# pi-crust14.net
KiCad netlist of a schematic drawn in EAGLE
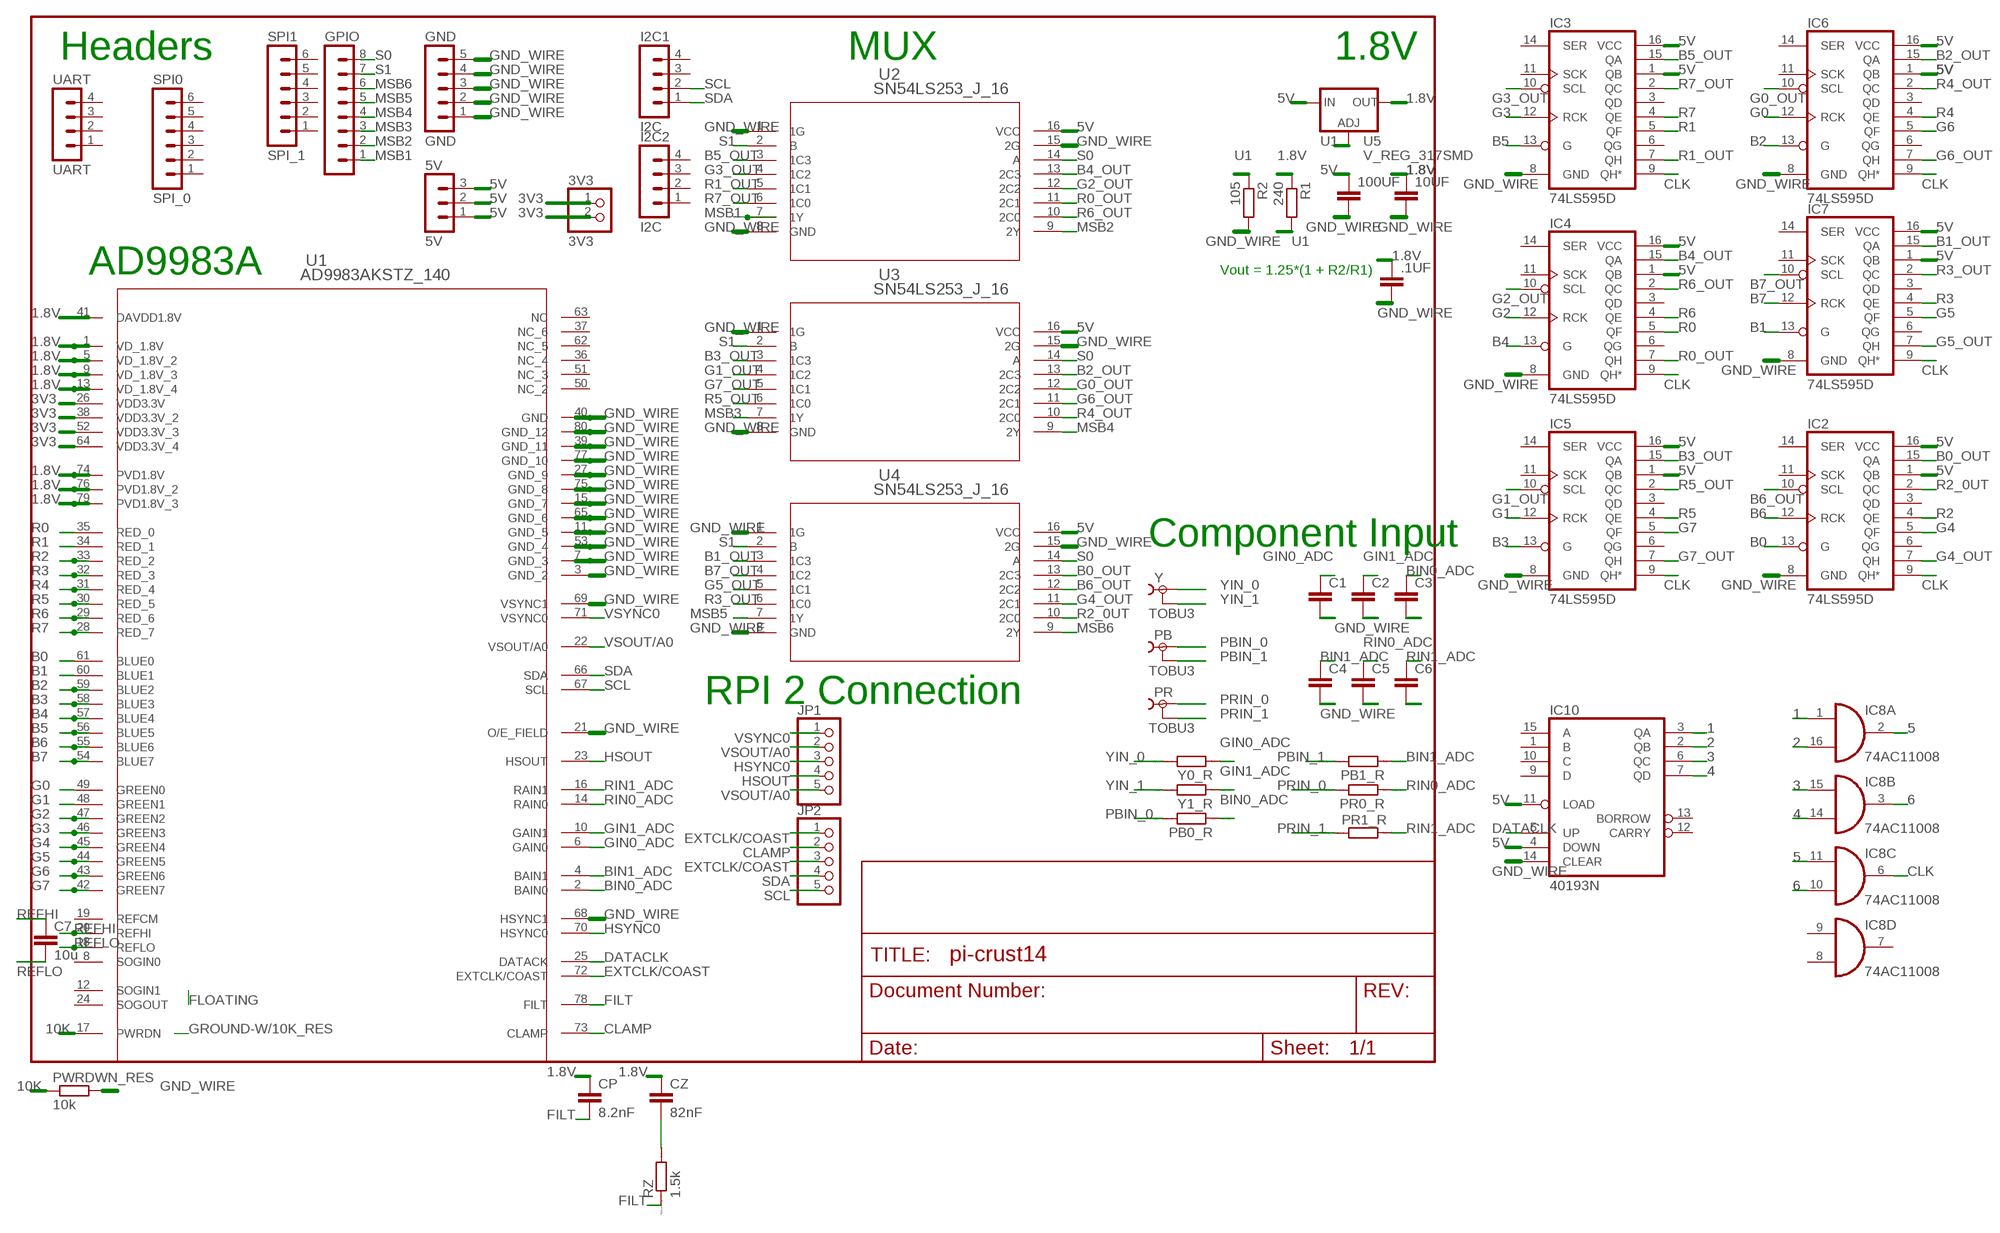
[diagram p0: schematic, sheet 1]

(export (version "E")
  (design (tool "Eeschema 10.0.6"))
  (components
    (comp (ref ".1UF")
      (value "C2.5/5")
      (footprint "eagle-import:C2.5-5")
      (libsource (lib "eagle-import") (part "C2.5/5"))
    )
    (comp (ref "3V3")
      (value "3V3")
      (footprint "eagle-import:1X02")
      (libsource (lib "eagle-import") (part "PINHD-1X2"))
    )
    (comp (ref "5V")
      (value "5V")
      (footprint "eagle-import:MA03-1")
      (libsource (lib "eagle-import") (part "MA03-1"))
    )
    (comp (ref "10UF")
      (value "C2.5/5")
      (footprint "eagle-import:C2.5-5")
      (libsource (lib "eagle-import") (part "C2.5/5"))
    )
    (comp (ref "100UF")
      (value "C2.5/5")
      (footprint "eagle-import:C2.5-5")
      (libsource (lib "eagle-import") (part "C2.5/5"))
    )
    (comp (ref "C1")
      (value "C2.5/5")
      (footprint "eagle-import:C2.5-5")
      (libsource (lib "eagle-import") (part "C2.5/5"))
    )
    (comp (ref "C2")
      (value "C2.5/5")
      (footprint "eagle-import:C2.5-5")
      (libsource (lib "eagle-import") (part "C2.5/5"))
    )
    (comp (ref "C3")
      (value "C2.5/5")
      (footprint "eagle-import:C2.5-5")
      (libsource (lib "eagle-import") (part "C2.5/5"))
    )
    (comp (ref "C4")
      (value "C2.5/5")
      (footprint "eagle-import:C2.5-5")
      (libsource (lib "eagle-import") (part "C2.5/5"))
    )
    (comp (ref "C5")
      (value "C2.5/5")
      (footprint "eagle-import:C2.5-5")
      (libsource (lib "eagle-import") (part "C2.5/5"))
    )
    (comp (ref "C6")
      (value "C2.5/5")
      (footprint "eagle-import:C2.5-5")
      (libsource (lib "eagle-import") (part "C2.5/5"))
    )
    (comp (ref "C7")
      (value "10u")
      (footprint "eagle-import:C2.5-5")
      (libsource (lib "eagle-import") (part "C2.5/5"))
    )
    (comp (ref "CP")
      (value "8.2nF")
      (footprint "eagle-import:C2.5-5")
      (libsource (lib "eagle-import") (part "C2.5/5"))
    )
    (comp (ref "CZ")
      (value "82nF")
      (footprint "eagle-import:C2.5-5")
      (libsource (lib "eagle-import") (part "C2.5/5"))
    )
    (comp (ref "GND")
      (value "GND")
      (footprint "eagle-import:MA05-1")
      (libsource (lib "eagle-import") (part "MA05-1"))
    )
    (comp (ref "GPIO")
      (value "MA08-1")
      (footprint "eagle-import:MA08-1")
      (libsource (lib "eagle-import") (part "MA08-1"))
    )
    (comp (ref "I2C1")
      (value "I2C")
      (footprint "eagle-import:MA04-1")
      (libsource (lib "eagle-import") (part "MA04-1"))
    )
    (comp (ref "I2C2")
      (value "I2C")
      (footprint "eagle-import:MA04-1")
      (libsource (lib "eagle-import") (part "MA04-1"))
    )
    (comp (ref "IC2")
      (value "74LS595D")
      (footprint "eagle-import:SO16")
      (libsource (lib "eagle-import") (part "74595DLS"))
    )
    (comp (ref "IC3")
      (value "74LS595D")
      (footprint "eagle-import:SO16")
      (libsource (lib "eagle-import") (part "74595DLS"))
    )
    (comp (ref "IC4")
      (value "74LS595D")
      (footprint "eagle-import:SO16")
      (libsource (lib "eagle-import") (part "74595DLS"))
    )
    (comp (ref "IC5")
      (value "74LS595D")
      (footprint "eagle-import:SO16")
      (libsource (lib "eagle-import") (part "74595DLS"))
    )
    (comp (ref "IC6")
      (value "74LS595D")
      (footprint "eagle-import:SO16")
      (libsource (lib "eagle-import") (part "74595DLS"))
    )
    (comp (ref "IC7")
      (value "74LS595D")
      (footprint "eagle-import:SO16")
      (libsource (lib "eagle-import") (part "74595DLS"))
    )
    (comp (ref "IC8")
      (value "74AC11008")
      (footprint "eagle-import:DIL16")
      (libsource (lib "eagle-import") (part "74AC11008"))
    )
    (comp (ref "IC10")
      (value "40193N")
      (footprint "eagle-import:DIL16")
      (libsource (lib "eagle-import") (part "40193N"))
    )
    (comp (ref "JP1")
      (value "PINHD-1X5")
      (footprint "eagle-import:1X05")
      (libsource (lib "eagle-import") (part "PINHD-1X5"))
    )
    (comp (ref "JP2")
      (value "PINHD-1X5")
      (footprint "eagle-import:1X05")
      (libsource (lib "eagle-import") (part "PINHD-1X5"))
    )
    (comp (ref "PB")
      (value "TOBU3")
      (footprint "eagle-import:TOBU3")
      (fields (field (name "MF") "FARNELL") (field (name "MPN") "TOBU 3"))
      (libsource (lib "eagle-import") (part "TOBU3"))
    )
    (comp (ref "PB0_R")
      (value "R0204/7")
      (footprint "eagle-import:0204_7")
      (libsource (lib "eagle-import") (part "R0204/7"))
    )
    (comp (ref "PB1_R")
      (value "R0204/7")
      (footprint "eagle-import:0204_7")
      (libsource (lib "eagle-import") (part "R0204/7"))
    )
    (comp (ref "PR")
      (value "TOBU3")
      (footprint "eagle-import:TOBU3")
      (fields (field (name "MF") "FARNELL") (field (name "MPN") "TOBU 3"))
      (libsource (lib "eagle-import") (part "TOBU3"))
    )
    (comp (ref "PR0_R")
      (value "R0204/7")
      (footprint "eagle-import:0204_7")
      (libsource (lib "eagle-import") (part "R0204/7"))
    )
    (comp (ref "PR1_R")
      (value "R0204/7")
      (footprint "eagle-import:0204_7")
      (libsource (lib "eagle-import") (part "R0204/7"))
    )
    (comp (ref "PWRDWN_RES")
      (value "10k")
      (footprint "eagle-import:0204_7")
      (libsource (lib "eagle-import") (part "R-EU_0204/7"))
    )
    (comp (ref "R1")
      (value "240")
      (footprint "eagle-import:0204_7")
      (libsource (lib "eagle-import") (part "R-EU_0204/7"))
    )
    (comp (ref "R2")
      (value "105")
      (footprint "eagle-import:0204_7")
      (libsource (lib "eagle-import") (part "R-EU_0204/7"))
    )
    (comp (ref "RZ")
      (value "1.5k")
      (footprint "eagle-import:0204_7")
      (libsource (lib "eagle-import") (part "R0204/7"))
    )
    (comp (ref "SPI0")
      (value "SPI_0")
      (footprint "eagle-import:MA06-1")
      (libsource (lib "eagle-import") (part "MA06-1"))
    )
    (comp (ref "SPI1")
      (value "SPI_1")
      (footprint "eagle-import:MA06-1")
      (libsource (lib "eagle-import") (part "MA06-1"))
    )
    (comp (ref "U1")
      (value "AD9983AKSTZ_140")
      (footprint "eagle-import:ST_80_2")
      (libsource (lib "eagle-import") (part "AD9983AKSTZ_140"))
    )
    (comp (ref "U2")
      (value "SN54LS253_J_16")
      (footprint "eagle-import:J16")
      (fields
        (field (name "GENERIC_PART_NUMBER") "SN54LS253")
        (field (name "MANUFACTURER") "Texas Instruments")
      )
      (libsource (lib "eagle-import") (part "SN54LS253_J_16"))
    )
    (comp (ref "U3")
      (value "SN54LS253_J_16")
      (footprint "eagle-import:J16")
      (fields
        (field (name "GENERIC_PART_NUMBER") "SN54LS253")
        (field (name "MANUFACTURER") "Texas Instruments")
      )
      (libsource (lib "eagle-import") (part "SN54LS253_J_16"))
    )
    (comp (ref "U4")
      (value "SN54LS253_J_16")
      (footprint "eagle-import:J16")
      (fields
        (field (name "GENERIC_PART_NUMBER") "SN54LS253")
        (field (name "MANUFACTURER") "Texas Instruments")
      )
      (libsource (lib "eagle-import") (part "SN54LS253_J_16"))
    )
    (comp (ref "U5")
      (value "V_REG_317SMD")
      (footprint "eagle-import:SOT223")
      (libsource (lib "eagle-import") (part "V_REG_317SMD"))
    )
    (comp (ref "UART")
      (value "UART")
      (footprint "eagle-import:MA04-1")
      (libsource (lib "eagle-import") (part "MA04-1"))
    )
    (comp (ref "Y")
      (value "TOBU3")
      (footprint "eagle-import:TOBU3")
      (fields (field (name "MF") "FARNELL") (field (name "MPN") "TOBU 3"))
      (libsource (lib "eagle-import") (part "TOBU3"))
    )
    (comp (ref "Y0_R")
      (value "R0204/7")
      (footprint "eagle-import:0204_7")
      (libsource (lib "eagle-import") (part "R0204/7"))
    )
    (comp (ref "Y1_R")
      (value "R0204/7")
      (footprint "eagle-import:0204_7")
      (libsource (lib "eagle-import") (part "R0204/7"))
    )
  )
  (nets
    (net (code "1") (name "/1") (class "Default")
      (node (ref "IC10") (pin "3") (pinfunction "QA_3") (pintype "output"))
      (node (ref "IC8") (pin "1") (pinfunction "I0_1") (pintype "input"))
    )
    (net (code "2") (name "/1.8V") (class "Default")
      (node (ref ".1UF") (pin "1") (pinfunction "1_1") (pintype "passive"))
      (node (ref "10UF") (pin "1") (pinfunction "1_1") (pintype "passive"))
      (node (ref "CP") (pin "1") (pinfunction "1_1") (pintype "passive"))
      (node (ref "CZ") (pin "1") (pinfunction "1_1") (pintype "passive"))
      (node (ref "R1") (pin "1") (pinfunction "1_1") (pintype "passive"))
      (node (ref "U1") (pin "1") (pinfunction "VD_1.8V_1") (pintype "passive"))
      (node (ref "U1") (pin "13") (pinfunction "VD_1.8V_4_13") (pintype "passive"))
      (node (ref "U1") (pin "41") (pinfunction "DAVDD1.8V_41") (pintype "passive"))
      (node (ref "U1") (pin "5") (pinfunction "VD_1.8V_2_5") (pintype "passive"))
      (node (ref "U1") (pin "74") (pinfunction "PVD1.8V_74") (pintype "passive"))
      (node (ref "U1") (pin "76") (pinfunction "PVD1.8V_2_76") (pintype "passive"))
      (node (ref "U1") (pin "79") (pinfunction "PVD1.8V_3_79") (pintype "passive"))
      (node (ref "U1") (pin "9") (pinfunction "VD_1.8V_3_9") (pintype "passive"))
      (node (ref "U5") (pin "2") (pinfunction "OUT_2") (pintype "output"))
    )
    (net (code "3") (name "/2") (class "Default")
      (node (ref "IC10") (pin "2") (pinfunction "QB_2") (pintype "output"))
      (node (ref "IC8") (pin "16") (pinfunction "I1_16") (pintype "input"))
    )
    (net (code "4") (name "/3") (class "Default")
      (node (ref "IC10") (pin "6") (pinfunction "QC_6") (pintype "output"))
      (node (ref "IC8") (pin "15") (pinfunction "I0_15") (pintype "input"))
    )
    (net (code "5") (name "/3V3") (class "Default")
      (node (ref "3V3") (pin "1") (pinfunction "1_1") (pintype "passive"))
      (node (ref "3V3") (pin "2") (pinfunction "2_2") (pintype "passive"))
      (node (ref "U1") (pin "26") (pinfunction "VDD3.3V_26") (pintype "passive"))
      (node (ref "U1") (pin "38") (pinfunction "VDD3.3V_2_38") (pintype "passive"))
      (node (ref "U1") (pin "52") (pinfunction "VDD3.3V_3_52") (pintype "passive"))
      (node (ref "U1") (pin "64") (pinfunction "VDD3.3V_4_64") (pintype "passive"))
    )
    (net (code "6") (name "/4") (class "Default")
      (node (ref "IC10") (pin "7") (pinfunction "QD_7") (pintype "output"))
      (node (ref "IC8") (pin "14") (pinfunction "I1_14") (pintype "input"))
    )
    (net (code "7") (name "/5") (class "Default")
      (node (ref "IC8") (pin "11") (pinfunction "I0_11") (pintype "input"))
      (node (ref "IC8") (pin "2") (pinfunction "O_2") (pintype "output"))
    )
    (net (code "8") (name "/5V") (class "Default")
      (node (ref "100UF") (pin "1") (pinfunction "1_1") (pintype "passive"))
      (node (ref "5V") (pin "1") (pinfunction "1_1") (pintype "passive"))
      (node (ref "5V") (pin "2") (pinfunction "2_2") (pintype "passive"))
      (node (ref "5V") (pin "3") (pinfunction "3_3") (pintype "passive"))
      (node (ref "IC10") (pin "11") (pinfunction "LOAD_11") (pintype "input"))
      (node (ref "IC10") (pin "4") (pinfunction "DOWN_4") (pintype "input"))
      (node (ref "IC2") (pin "1") (pinfunction "QB_1") (pintype "tri_state"))
      (node (ref "IC2") (pin "16") (pinfunction "VCC_16") (pintype "power_in"))
      (node (ref "IC3") (pin "1") (pinfunction "QB_1") (pintype "tri_state"))
      (node (ref "IC3") (pin "16") (pinfunction "VCC_16") (pintype "power_in"))
      (node (ref "IC4") (pin "1") (pinfunction "QB_1") (pintype "tri_state"))
      (node (ref "IC4") (pin "16") (pinfunction "VCC_16") (pintype "power_in"))
      (node (ref "IC5") (pin "1") (pinfunction "QB_1") (pintype "tri_state"))
      (node (ref "IC5") (pin "16") (pinfunction "VCC_16") (pintype "power_in"))
      (node (ref "IC6") (pin "1") (pinfunction "QB_1") (pintype "tri_state"))
      (node (ref "IC6") (pin "16") (pinfunction "VCC_16") (pintype "power_in"))
      (node (ref "IC7") (pin "1") (pinfunction "QB_1") (pintype "tri_state"))
      (node (ref "IC7") (pin "16") (pinfunction "VCC_16") (pintype "power_in"))
      (node (ref "U2") (pin "16") (pinfunction "VCC_16") (pintype "power_in"))
      (node (ref "U3") (pin "16") (pinfunction "VCC_16") (pintype "power_in"))
      (node (ref "U4") (pin "16") (pinfunction "VCC_16") (pintype "power_in"))
      (node (ref "U5") (pin "3") (pinfunction "IN_3") (pintype "input"))
    )
    (net (code "9") (name "/6") (class "Default")
      (node (ref "IC8") (pin "10") (pinfunction "I1_10") (pintype "input"))
      (node (ref "IC8") (pin "3") (pinfunction "O_3") (pintype "output"))
    )
    (net (code "10") (name "/10K") (class "Default")
      (node (ref "PWRDWN_RES") (pin "1") (pinfunction "1_1") (pintype "passive"))
      (node (ref "U1") (pin "17") (pinfunction "PWRDN_17") (pintype "passive"))
    )
    (net (code "11") (name "/B0") (class "Default")
      (node (ref "IC2") (pin "13") (pinfunction "G_13") (pintype "input"))
      (node (ref "U1") (pin "61") (pinfunction "BLUE0_61") (pintype "passive"))
    )
    (net (code "12") (name "/B0_OUT") (class "Default")
      (node (ref "IC2") (pin "15") (pinfunction "QA_15") (pintype "tri_state"))
      (node (ref "U4") (pin "13") (pinfunction "2C3_13") (pintype "input"))
    )
    (net (code "13") (name "/B1") (class "Default")
      (node (ref "IC7") (pin "13") (pinfunction "G_13") (pintype "input"))
      (node (ref "U1") (pin "60") (pinfunction "BLUE1_60") (pintype "passive"))
    )
    (net (code "14") (name "/B1_OUT") (class "Default")
      (node (ref "IC7") (pin "15") (pinfunction "QA_15") (pintype "tri_state"))
      (node (ref "U4") (pin "3") (pinfunction "1C3_3") (pintype "input"))
    )
    (net (code "15") (name "/B2") (class "Default")
      (node (ref "IC6") (pin "13") (pinfunction "G_13") (pintype "input"))
      (node (ref "U1") (pin "59") (pinfunction "BLUE2_59") (pintype "passive"))
    )
    (net (code "16") (name "/B2_OUT") (class "Default")
      (node (ref "IC6") (pin "15") (pinfunction "QA_15") (pintype "tri_state"))
      (node (ref "U3") (pin "13") (pinfunction "2C3_13") (pintype "input"))
    )
    (net (code "17") (name "/B3") (class "Default")
      (node (ref "IC5") (pin "13") (pinfunction "G_13") (pintype "input"))
      (node (ref "U1") (pin "58") (pinfunction "BLUE3_58") (pintype "passive"))
    )
    (net (code "18") (name "/B3_OUT") (class "Default")
      (node (ref "IC5") (pin "15") (pinfunction "QA_15") (pintype "tri_state"))
      (node (ref "U3") (pin "3") (pinfunction "1C3_3") (pintype "input"))
    )
    (net (code "19") (name "/B4") (class "Default")
      (node (ref "IC4") (pin "13") (pinfunction "G_13") (pintype "input"))
      (node (ref "U1") (pin "57") (pinfunction "BLUE4_57") (pintype "passive"))
    )
    (net (code "20") (name "/B4_OUT") (class "Default")
      (node (ref "IC4") (pin "15") (pinfunction "QA_15") (pintype "tri_state"))
      (node (ref "U2") (pin "13") (pinfunction "2C3_13") (pintype "input"))
    )
    (net (code "21") (name "/B5") (class "Default")
      (node (ref "IC3") (pin "13") (pinfunction "G_13") (pintype "input"))
      (node (ref "U1") (pin "56") (pinfunction "BLUE5_56") (pintype "passive"))
    )
    (net (code "22") (name "/B5_OUT") (class "Default")
      (node (ref "IC3") (pin "15") (pinfunction "QA_15") (pintype "tri_state"))
      (node (ref "U2") (pin "3") (pinfunction "1C3_3") (pintype "input"))
    )
    (net (code "23") (name "/B6") (class "Default")
      (node (ref "IC2") (pin "12") (pinfunction "RCK_12") (pintype "input"))
      (node (ref "U1") (pin "55") (pinfunction "BLUE6_55") (pintype "passive"))
    )
    (net (code "24") (name "/B6_OUT") (class "Default")
      (node (ref "IC2") (pin "10") (pinfunction "SCL_10") (pintype "input"))
      (node (ref "U4") (pin "12") (pinfunction "2C2_12") (pintype "input"))
    )
    (net (code "25") (name "/B7") (class "Default")
      (node (ref "IC7") (pin "12") (pinfunction "RCK_12") (pintype "input"))
      (node (ref "U1") (pin "54") (pinfunction "BLUE7_54") (pintype "passive"))
    )
    (net (code "26") (name "/B7_OUT") (class "Default")
      (node (ref "IC7") (pin "10") (pinfunction "SCL_10") (pintype "input"))
      (node (ref "U4") (pin "4") (pinfunction "1C2_4") (pintype "input"))
    )
    (net (code "27") (name "/BIN0_ADC") (class "Default")
      (node (ref "C3") (pin "1") (pinfunction "1_1") (pintype "passive"))
      (node (ref "PB0_R") (pin "1") (pinfunction "1_1") (pintype "passive"))
      (node (ref "U1") (pin "2") (pinfunction "BAIN0_2") (pintype "passive"))
    )
    (net (code "28") (name "/BIN1_ADC") (class "Default")
      (node (ref "C4") (pin "1") (pinfunction "1_1") (pintype "passive"))
      (node (ref "PB1_R") (pin "1") (pinfunction "1_1") (pintype "passive"))
      (node (ref "U1") (pin "4") (pinfunction "BAIN1_4") (pintype "passive"))
    )
    (net (code "29") (name "/CLAMP") (class "Default")
      (node (ref "JP2") (pin "2") (pinfunction "2_2") (pintype "passive"))
      (node (ref "U1") (pin "73") (pinfunction "CLAMP_73") (pintype "passive"))
    )
    (net (code "30") (name "/CLK") (class "Default")
      (node (ref "IC2") (pin "9") (pinfunction "QH*_9") (pintype "tri_state"))
      (node (ref "IC3") (pin "9") (pinfunction "QH*_9") (pintype "tri_state"))
      (node (ref "IC4") (pin "9") (pinfunction "QH*_9") (pintype "tri_state"))
      (node (ref "IC5") (pin "9") (pinfunction "QH*_9") (pintype "tri_state"))
      (node (ref "IC6") (pin "9") (pinfunction "QH*_9") (pintype "tri_state"))
      (node (ref "IC7") (pin "9") (pinfunction "QH*_9") (pintype "tri_state"))
      (node (ref "IC8") (pin "6") (pinfunction "O_6") (pintype "output"))
    )
    (net (code "31") (name "/DATACLK") (class "Default")
      (node (ref "IC10") (pin "5") (pinfunction "UP_5") (pintype "input"))
      (node (ref "U1") (pin "25") (pinfunction "DATACK_25") (pintype "passive"))
    )
    (net (code "32") (name "/EXTCLK{slash}COAST") (class "Default")
      (node (ref "JP2") (pin "1") (pinfunction "1_1") (pintype "passive"))
      (node (ref "JP2") (pin "3") (pinfunction "3_3") (pintype "passive"))
      (node (ref "U1") (pin "72") (pinfunction "EXTCLK/COAST_72") (pintype "passive"))
    )
    (net (code "33") (name "/FILT") (class "Default")
      (node (ref "CP") (pin "2") (pinfunction "2_2") (pintype "passive"))
      (node (ref "RZ") (pin "1") (pinfunction "1_1") (pintype "passive"))
      (node (ref "U1") (pin "78") (pinfunction "FILT_78") (pintype "passive"))
    )
    (net (code "35") (name "/G0") (class "Default")
      (node (ref "IC6") (pin "12") (pinfunction "RCK_12") (pintype "input"))
      (node (ref "U1") (pin "49") (pinfunction "GREEN0_49") (pintype "passive"))
    )
    (net (code "36") (name "/G0_OUT") (class "Default")
      (node (ref "IC6") (pin "10") (pinfunction "SCL_10") (pintype "input"))
      (node (ref "U3") (pin "12") (pinfunction "2C2_12") (pintype "input"))
    )
    (net (code "37") (name "/G1") (class "Default")
      (node (ref "IC5") (pin "12") (pinfunction "RCK_12") (pintype "input"))
      (node (ref "U1") (pin "48") (pinfunction "GREEN1_48") (pintype "passive"))
    )
    (net (code "38") (name "/G1_OUT") (class "Default")
      (node (ref "IC5") (pin "10") (pinfunction "SCL_10") (pintype "input"))
      (node (ref "U3") (pin "4") (pinfunction "1C2_4") (pintype "input"))
    )
    (net (code "39") (name "/G2") (class "Default")
      (node (ref "IC4") (pin "12") (pinfunction "RCK_12") (pintype "input"))
      (node (ref "U1") (pin "47") (pinfunction "GREEN2_47") (pintype "passive"))
    )
    (net (code "40") (name "/G2_OUT") (class "Default")
      (node (ref "IC4") (pin "10") (pinfunction "SCL_10") (pintype "input"))
      (node (ref "U2") (pin "12") (pinfunction "2C2_12") (pintype "input"))
    )
    (net (code "41") (name "/G3") (class "Default")
      (node (ref "IC3") (pin "12") (pinfunction "RCK_12") (pintype "input"))
      (node (ref "U1") (pin "46") (pinfunction "GREEN3_46") (pintype "passive"))
    )
    (net (code "42") (name "/G3_OUT") (class "Default")
      (node (ref "IC3") (pin "10") (pinfunction "SCL_10") (pintype "input"))
      (node (ref "U2") (pin "4") (pinfunction "1C2_4") (pintype "input"))
    )
    (net (code "43") (name "/G4") (class "Default")
      (node (ref "IC2") (pin "5") (pinfunction "QF_5") (pintype "tri_state"))
      (node (ref "U1") (pin "45") (pinfunction "GREEN4_45") (pintype "passive"))
    )
    (net (code "44") (name "/G4_OUT") (class "Default")
      (node (ref "IC2") (pin "7") (pinfunction "QH_7") (pintype "tri_state"))
      (node (ref "U4") (pin "11") (pinfunction "2C1_11") (pintype "input"))
    )
    (net (code "45") (name "/G5") (class "Default")
      (node (ref "IC7") (pin "5") (pinfunction "QF_5") (pintype "tri_state"))
      (node (ref "U1") (pin "44") (pinfunction "GREEN5_44") (pintype "passive"))
    )
    (net (code "46") (name "/G5_OUT") (class "Default")
      (node (ref "IC7") (pin "7") (pinfunction "QH_7") (pintype "tri_state"))
      (node (ref "U4") (pin "5") (pinfunction "1C1_5") (pintype "input"))
    )
    (net (code "47") (name "/G6") (class "Default")
      (node (ref "IC6") (pin "5") (pinfunction "QF_5") (pintype "tri_state"))
      (node (ref "U1") (pin "43") (pinfunction "GREEN6_43") (pintype "passive"))
    )
    (net (code "48") (name "/G6_OUT") (class "Default")
      (node (ref "IC6") (pin "7") (pinfunction "QH_7") (pintype "tri_state"))
      (node (ref "U3") (pin "11") (pinfunction "2C1_11") (pintype "input"))
    )
    (net (code "49") (name "/G7") (class "Default")
      (node (ref "IC5") (pin "5") (pinfunction "QF_5") (pintype "tri_state"))
      (node (ref "U1") (pin "42") (pinfunction "GREEN7_42") (pintype "passive"))
    )
    (net (code "50") (name "/G7_OUT") (class "Default")
      (node (ref "IC5") (pin "7") (pinfunction "QH_7") (pintype "tri_state"))
      (node (ref "U3") (pin "5") (pinfunction "1C1_5") (pintype "input"))
    )
    (net (code "51") (name "/GIN0_ADC") (class "Default")
      (node (ref "C1") (pin "1") (pinfunction "1_1") (pintype "passive"))
      (node (ref "U1") (pin "6") (pinfunction "GAIN0_6") (pintype "passive"))
      (node (ref "Y0_R") (pin "1") (pinfunction "1_1") (pintype "passive"))
    )
    (net (code "52") (name "/GIN1_ADC") (class "Default")
      (node (ref "C2") (pin "1") (pinfunction "1_1") (pintype "passive"))
      (node (ref "U1") (pin "10") (pinfunction "GAIN1_10") (pintype "passive"))
      (node (ref "Y1_R") (pin "1") (pinfunction "1_1") (pintype "passive"))
    )
    (net (code "53") (name "/GND_WIRE") (class "Default")
      (node (ref ".1UF") (pin "2") (pinfunction "2_2") (pintype "passive"))
      (node (ref "100UF") (pin "2") (pinfunction "2_2") (pintype "passive"))
      (node (ref "10UF") (pin "2") (pinfunction "2_2") (pintype "passive"))
      (node (ref "C1") (pin "2") (pinfunction "2_2") (pintype "passive"))
      (node (ref "C2") (pin "2") (pinfunction "2_2") (pintype "passive"))
      (node (ref "C3") (pin "2") (pinfunction "2_2") (pintype "passive"))
      (node (ref "C4") (pin "2") (pinfunction "2_2") (pintype "passive"))
      (node (ref "C5") (pin "2") (pinfunction "2_2") (pintype "passive"))
      (node (ref "C6") (pin "2") (pinfunction "2_2") (pintype "passive"))
      (node (ref "GND") (pin "1") (pinfunction "1_1") (pintype "passive"))
      (node (ref "GND") (pin "2") (pinfunction "2_2") (pintype "passive"))
      (node (ref "GND") (pin "3") (pinfunction "3_3") (pintype "passive"))
      (node (ref "GND") (pin "4") (pinfunction "4_4") (pintype "passive"))
      (node (ref "GND") (pin "5") (pinfunction "5_5") (pintype "passive"))
      (node (ref "IC10") (pin "14") (pinfunction "CLEAR_14") (pintype "input"))
      (node (ref "IC2") (pin "8") (pinfunction "GND_8") (pintype "power_in"))
      (node (ref "IC3") (pin "8") (pinfunction "GND_8") (pintype "power_in"))
      (node (ref "IC4") (pin "8") (pinfunction "GND_8") (pintype "power_in"))
      (node (ref "IC5") (pin "8") (pinfunction "GND_8") (pintype "power_in"))
      (node (ref "IC6") (pin "8") (pinfunction "GND_8") (pintype "power_in"))
      (node (ref "IC7") (pin "8") (pinfunction "GND_8") (pintype "power_in"))
      (node (ref "PWRDWN_RES") (pin "2") (pinfunction "2_2") (pintype "passive"))
      (node (ref "R2") (pin "2") (pinfunction "2_2") (pintype "passive"))
      (node (ref "U1") (pin "11") (pinfunction "GND_5_11") (pintype "passive"))
      (node (ref "U1") (pin "15") (pinfunction "GND_7_15") (pintype "passive"))
      (node (ref "U1") (pin "21") (pinfunction "O/E_FIELD_21") (pintype "passive"))
      (node (ref "U1") (pin "27") (pinfunction "GND_9_27") (pintype "passive"))
      (node (ref "U1") (pin "3") (pinfunction "GND_2_3") (pintype "passive"))
      (node (ref "U1") (pin "39") (pinfunction "GND_11_39") (pintype "passive"))
      (node (ref "U1") (pin "40") (pinfunction "GND_40") (pintype "passive"))
      (node (ref "U1") (pin "53") (pinfunction "GND_4_53") (pintype "passive"))
      (node (ref "U1") (pin "65") (pinfunction "GND_6_65") (pintype "passive"))
      (node (ref "U1") (pin "68") (pinfunction "HSYNC1_68") (pintype "passive"))
      (node (ref "U1") (pin "69") (pinfunction "VSYNC1_69") (pintype "passive"))
      (node (ref "U1") (pin "7") (pinfunction "GND_3_7") (pintype "passive"))
      (node (ref "U1") (pin "75") (pinfunction "GND_8_75") (pintype "passive"))
      (node (ref "U1") (pin "77") (pinfunction "GND_10_77") (pintype "passive"))
      (node (ref "U1") (pin "80") (pinfunction "GND_12_80") (pintype "passive"))
      (node (ref "U2") (pin "1") (pinfunction "1G_1") (pintype "input"))
      (node (ref "U2") (pin "15") (pinfunction "2G_15") (pintype "input"))
      (node (ref "U2") (pin "8") (pinfunction "GND_8") (pintype "power_in"))
      (node (ref "U3") (pin "1") (pinfunction "1G_1") (pintype "input"))
      (node (ref "U3") (pin "15") (pinfunction "2G_15") (pintype "input"))
      (node (ref "U3") (pin "8") (pinfunction "GND_8") (pintype "power_in"))
      (node (ref "U4") (pin "1") (pinfunction "1G_1") (pintype "input"))
      (node (ref "U4") (pin "15") (pinfunction "2G_15") (pintype "input"))
      (node (ref "U4") (pin "8") (pinfunction "GND_8") (pintype "power_in"))
    )
    (net (code "55") (name "/HSOUT") (class "Default")
      (node (ref "JP1") (pin "4") (pinfunction "4_4") (pintype "passive"))
      (node (ref "U1") (pin "23") (pinfunction "HSOUT_23") (pintype "passive"))
    )
    (net (code "56") (name "/HSYNC0") (class "Default")
      (node (ref "JP1") (pin "3") (pinfunction "3_3") (pintype "passive"))
      (node (ref "U1") (pin "70") (pinfunction "HSYNC0_70") (pintype "passive"))
    )
    (net (code "57") (name "/MSB1") (class "Default")
      (node (ref "GPIO") (pin "1") (pinfunction "1_1") (pintype "passive"))
      (node (ref "U2") (pin "7") (pinfunction "1Y_7") (pintype "output"))
    )
    (net (code "58") (name "/MSB2") (class "Default")
      (node (ref "GPIO") (pin "2") (pinfunction "2_2") (pintype "passive"))
      (node (ref "U2") (pin "9") (pinfunction "2Y_9") (pintype "output"))
    )
    (net (code "59") (name "/MSB3") (class "Default")
      (node (ref "GPIO") (pin "3") (pinfunction "3_3") (pintype "passive"))
      (node (ref "U3") (pin "7") (pinfunction "1Y_7") (pintype "output"))
    )
    (net (code "60") (name "/MSB4") (class "Default")
      (node (ref "GPIO") (pin "4") (pinfunction "4_4") (pintype "passive"))
      (node (ref "U3") (pin "9") (pinfunction "2Y_9") (pintype "output"))
    )
    (net (code "61") (name "/MSB5") (class "Default")
      (node (ref "GPIO") (pin "5") (pinfunction "5_5") (pintype "passive"))
      (node (ref "U4") (pin "7") (pinfunction "1Y_7") (pintype "output"))
    )
    (net (code "62") (name "/MSB6") (class "Default")
      (node (ref "GPIO") (pin "6") (pinfunction "6_6") (pintype "passive"))
      (node (ref "U4") (pin "9") (pinfunction "2Y_9") (pintype "output"))
    )
    (net (code "63") (name "/PBIN_0") (class "Default")
      (node (ref "PB") (pin "1") (pinfunction "1_1") (pintype "passive"))
      (node (ref "PB0_R") (pin "2") (pinfunction "2_2") (pintype "passive"))
    )
    (net (code "64") (name "/PBIN_1") (class "Default")
      (node (ref "PB") (pin "2") (pinfunction "2_2") (pintype "passive"))
      (node (ref "PB") (pin "2@1") (pinfunction "2_2@1") (pintype "passive"))
      (node (ref "PB") (pin "2@2") (pinfunction "2_2@2") (pintype "passive"))
      (node (ref "PB1_R") (pin "2") (pinfunction "2_2") (pintype "passive"))
    )
    (net (code "65") (name "/PRIN_0") (class "Default")
      (node (ref "PR") (pin "1") (pinfunction "1_1") (pintype "passive"))
      (node (ref "PR0_R") (pin "2") (pinfunction "2_2") (pintype "passive"))
    )
    (net (code "66") (name "/PRIN_1") (class "Default")
      (node (ref "PR") (pin "2") (pinfunction "2_2") (pintype "passive"))
      (node (ref "PR") (pin "2@1") (pinfunction "2_2@1") (pintype "passive"))
      (node (ref "PR") (pin "2@2") (pinfunction "2_2@2") (pintype "passive"))
      (node (ref "PR1_R") (pin "1") (pinfunction "1_1") (pintype "passive"))
    )
    (net (code "67") (name "/R0") (class "Default")
      (node (ref "IC4") (pin "5") (pinfunction "QF_5") (pintype "tri_state"))
      (node (ref "U1") (pin "35") (pinfunction "RED_0_35") (pintype "passive"))
    )
    (net (code "68") (name "/R0_OUT") (class "Default")
      (node (ref "IC4") (pin "7") (pinfunction "QH_7") (pintype "tri_state"))
      (node (ref "U2") (pin "11") (pinfunction "2C1_11") (pintype "input"))
    )
    (net (code "69") (name "/R1") (class "Default")
      (node (ref "IC3") (pin "5") (pinfunction "QF_5") (pintype "tri_state"))
      (node (ref "U1") (pin "34") (pinfunction "RED_1_34") (pintype "passive"))
    )
    (net (code "70") (name "/R1_OUT") (class "Default")
      (node (ref "IC3") (pin "7") (pinfunction "QH_7") (pintype "tri_state"))
      (node (ref "U2") (pin "5") (pinfunction "1C1_5") (pintype "input"))
    )
    (net (code "71") (name "/R2") (class "Default")
      (node (ref "IC2") (pin "4") (pinfunction "QE_4") (pintype "tri_state"))
      (node (ref "U1") (pin "33") (pinfunction "RED_2_33") (pintype "passive"))
    )
    (net (code "72") (name "/R2_0UT") (class "Default")
      (node (ref "IC2") (pin "2") (pinfunction "QC_2") (pintype "tri_state"))
      (node (ref "U4") (pin "10") (pinfunction "2C0_10") (pintype "input"))
    )
    (net (code "73") (name "/R3") (class "Default")
      (node (ref "IC7") (pin "4") (pinfunction "QE_4") (pintype "tri_state"))
      (node (ref "U1") (pin "32") (pinfunction "RED_3_32") (pintype "passive"))
    )
    (net (code "74") (name "/R3_OUT") (class "Default")
      (node (ref "IC7") (pin "2") (pinfunction "QC_2") (pintype "tri_state"))
      (node (ref "U4") (pin "6") (pinfunction "1C0_6") (pintype "input"))
    )
    (net (code "75") (name "/R4") (class "Default")
      (node (ref "IC6") (pin "4") (pinfunction "QE_4") (pintype "tri_state"))
      (node (ref "U1") (pin "31") (pinfunction "RED_4_31") (pintype "passive"))
    )
    (net (code "76") (name "/R4_OUT") (class "Default")
      (node (ref "IC6") (pin "2") (pinfunction "QC_2") (pintype "tri_state"))
      (node (ref "U3") (pin "10") (pinfunction "2C0_10") (pintype "input"))
    )
    (net (code "77") (name "/R5") (class "Default")
      (node (ref "IC5") (pin "4") (pinfunction "QE_4") (pintype "tri_state"))
      (node (ref "U1") (pin "30") (pinfunction "RED_5_30") (pintype "passive"))
    )
    (net (code "78") (name "/R5_OUT") (class "Default")
      (node (ref "IC5") (pin "2") (pinfunction "QC_2") (pintype "tri_state"))
      (node (ref "U3") (pin "6") (pinfunction "1C0_6") (pintype "input"))
    )
    (net (code "79") (name "/R6") (class "Default")
      (node (ref "IC4") (pin "4") (pinfunction "QE_4") (pintype "tri_state"))
      (node (ref "U1") (pin "29") (pinfunction "RED_6_29") (pintype "passive"))
    )
    (net (code "80") (name "/R6_OUT") (class "Default")
      (node (ref "IC4") (pin "2") (pinfunction "QC_2") (pintype "tri_state"))
      (node (ref "U2") (pin "10") (pinfunction "2C0_10") (pintype "input"))
    )
    (net (code "81") (name "/R7") (class "Default")
      (node (ref "IC3") (pin "4") (pinfunction "QE_4") (pintype "tri_state"))
      (node (ref "U1") (pin "28") (pinfunction "RED_7_28") (pintype "passive"))
    )
    (net (code "82") (name "/R7_OUT") (class "Default")
      (node (ref "IC3") (pin "2") (pinfunction "QC_2") (pintype "tri_state"))
      (node (ref "U2") (pin "6") (pinfunction "1C0_6") (pintype "input"))
    )
    (net (code "83") (name "/REFHI") (class "Default")
      (node (ref "C7") (pin "1") (pinfunction "1_1") (pintype "passive"))
      (node (ref "U1") (pin "20") (pinfunction "REFHI_20") (pintype "passive"))
    )
    (net (code "84") (name "/REFLO") (class "Default")
      (node (ref "C7") (pin "2") (pinfunction "2_2") (pintype "passive"))
      (node (ref "U1") (pin "18") (pinfunction "REFLO_18") (pintype "passive"))
    )
    (net (code "85") (name "/RIN0_ADC") (class "Default")
      (node (ref "C5") (pin "1") (pinfunction "1_1") (pintype "passive"))
      (node (ref "PR0_R") (pin "1") (pinfunction "1_1") (pintype "passive"))
      (node (ref "U1") (pin "14") (pinfunction "RAIN0_14") (pintype "passive"))
    )
    (net (code "86") (name "/RIN1_ADC") (class "Default")
      (node (ref "C6") (pin "1") (pinfunction "1_1") (pintype "passive"))
      (node (ref "PR1_R") (pin "2") (pinfunction "2_2") (pintype "passive"))
      (node (ref "U1") (pin "16") (pinfunction "RAIN1_16") (pintype "passive"))
    )
    (net (code "87") (name "/S0") (class "Default")
      (node (ref "GPIO") (pin "8") (pinfunction "8_8") (pintype "passive"))
      (node (ref "U2") (pin "14") (pinfunction "A_14") (pintype "input"))
      (node (ref "U3") (pin "14") (pinfunction "A_14") (pintype "input"))
      (node (ref "U4") (pin "14") (pinfunction "A_14") (pintype "input"))
    )
    (net (code "88") (name "/S1") (class "Default")
      (node (ref "GPIO") (pin "7") (pinfunction "7_7") (pintype "passive"))
      (node (ref "U2") (pin "2") (pinfunction "B_2") (pintype "input"))
      (node (ref "U3") (pin "2") (pinfunction "B_2") (pintype "input"))
      (node (ref "U4") (pin "2") (pinfunction "B_2") (pintype "input"))
    )
    (net (code "89") (name "/SCL") (class "Default")
      (node (ref "I2C1") (pin "2") (pinfunction "2_2") (pintype "passive"))
      (node (ref "JP2") (pin "5") (pinfunction "5_5") (pintype "passive"))
      (node (ref "U1") (pin "67") (pinfunction "SCL_67") (pintype "passive"))
    )
    (net (code "90") (name "/SDA") (class "Default")
      (node (ref "I2C1") (pin "1") (pinfunction "1_1") (pintype "passive"))
      (node (ref "JP2") (pin "4") (pinfunction "4_4") (pintype "passive"))
      (node (ref "U1") (pin "66") (pinfunction "SDA_66") (pintype "passive"))
    )
    (net (code "91") (name "/U1") (class "Default")
      (node (ref "R1") (pin "2") (pinfunction "2_2") (pintype "passive"))
      (node (ref "R2") (pin "1") (pinfunction "1_1") (pintype "passive"))
      (node (ref "U5") (pin "1") (pinfunction "ADJ_1") (pintype "input"))
    )
    (net (code "92") (name "/VSOUT{slash}A0") (class "Default")
      (node (ref "JP1") (pin "2") (pinfunction "2_2") (pintype "passive"))
      (node (ref "JP1") (pin "5") (pinfunction "5_5") (pintype "passive"))
      (node (ref "U1") (pin "22") (pinfunction "VSOUT/A0_22") (pintype "passive"))
    )
    (net (code "93") (name "/VSYNC0") (class "Default")
      (node (ref "JP1") (pin "1") (pinfunction "1_1") (pintype "passive"))
      (node (ref "U1") (pin "71") (pinfunction "VSYNC0_71") (pintype "passive"))
    )
    (net (code "94") (name "/YIN_0") (class "Default")
      (node (ref "Y") (pin "1") (pinfunction "1_1") (pintype "passive"))
      (node (ref "Y0_R") (pin "2") (pinfunction "2_2") (pintype "passive"))
    )
    (net (code "95") (name "/YIN_1") (class "Default")
      (node (ref "Y") (pin "2") (pinfunction "2_2") (pintype "passive"))
      (node (ref "Y") (pin "2@1") (pinfunction "2_2@1") (pintype "passive"))
      (node (ref "Y") (pin "2@2") (pinfunction "2_2@2") (pintype "passive"))
      (node (ref "Y1_R") (pin "2") (pinfunction "2_2") (pintype "passive"))
    )
    (net (code "96") (name "Net-(CZ-Pad2)") (class "Default")
      (node (ref "CZ") (pin "2") (pinfunction "2_2") (pintype "passive"))
      (node (ref "RZ") (pin "2") (pinfunction "2_2") (pintype "passive"))
    )
    (net (code "97") (name "unconnected-(I2C1-Pad3)") (class "Default")
      (node (ref "I2C1") (pin "3") (pinfunction "3_3") (pintype "passive"))
    )
    (net (code "98") (name "unconnected-(I2C1-Pad4)") (class "Default")
      (node (ref "I2C1") (pin "4") (pinfunction "4_4") (pintype "passive"))
    )
    (net (code "99") (name "unconnected-(I2C2-Pad1)") (class "Default")
      (node (ref "I2C2") (pin "1") (pinfunction "1_1") (pintype "passive"))
    )
    (net (code "100") (name "unconnected-(I2C2-Pad2)") (class "Default")
      (node (ref "I2C2") (pin "2") (pinfunction "2_2") (pintype "passive"))
    )
    (net (code "101") (name "unconnected-(I2C2-Pad3)") (class "Default")
      (node (ref "I2C2") (pin "3") (pinfunction "3_3") (pintype "passive"))
    )
    (net (code "102") (name "unconnected-(I2C2-Pad4)") (class "Default")
      (node (ref "I2C2") (pin "4") (pinfunction "4_4") (pintype "passive"))
    )
    (net (code "103") (name "unconnected-(IC2-QD-Pad3)") (class "Default")
      (node (ref "IC2") (pin "3") (pinfunction "QD_3") (pintype "tri_state"))
    )
    (net (code "104") (name "unconnected-(IC2-QG-Pad6)") (class "Default")
      (node (ref "IC2") (pin "6") (pinfunction "QG_6") (pintype "tri_state"))
    )
    (net (code "105") (name "unconnected-(IC2-SCK-Pad11)") (class "Default")
      (node (ref "IC2") (pin "11") (pinfunction "SCK_11") (pintype "input"))
    )
    (net (code "106") (name "unconnected-(IC2-SER-Pad14)") (class "Default")
      (node (ref "IC2") (pin "14") (pinfunction "SER_14") (pintype "input"))
    )
    (net (code "107") (name "unconnected-(IC3-QD-Pad3)") (class "Default")
      (node (ref "IC3") (pin "3") (pinfunction "QD_3") (pintype "tri_state"))
    )
    (net (code "108") (name "unconnected-(IC3-QG-Pad6)") (class "Default")
      (node (ref "IC3") (pin "6") (pinfunction "QG_6") (pintype "tri_state"))
    )
    (net (code "109") (name "unconnected-(IC3-SCK-Pad11)") (class "Default")
      (node (ref "IC3") (pin "11") (pinfunction "SCK_11") (pintype "input"))
    )
    (net (code "110") (name "unconnected-(IC3-SER-Pad14)") (class "Default")
      (node (ref "IC3") (pin "14") (pinfunction "SER_14") (pintype "input"))
    )
    (net (code "111") (name "unconnected-(IC4-QD-Pad3)") (class "Default")
      (node (ref "IC4") (pin "3") (pinfunction "QD_3") (pintype "tri_state"))
    )
    (net (code "112") (name "unconnected-(IC4-QG-Pad6)") (class "Default")
      (node (ref "IC4") (pin "6") (pinfunction "QG_6") (pintype "tri_state"))
    )
    (net (code "113") (name "unconnected-(IC4-SCK-Pad11)") (class "Default")
      (node (ref "IC4") (pin "11") (pinfunction "SCK_11") (pintype "input"))
    )
    (net (code "114") (name "unconnected-(IC4-SER-Pad14)") (class "Default")
      (node (ref "IC4") (pin "14") (pinfunction "SER_14") (pintype "input"))
    )
    (net (code "115") (name "unconnected-(IC5-QD-Pad3)") (class "Default")
      (node (ref "IC5") (pin "3") (pinfunction "QD_3") (pintype "tri_state"))
    )
    (net (code "116") (name "unconnected-(IC5-QG-Pad6)") (class "Default")
      (node (ref "IC5") (pin "6") (pinfunction "QG_6") (pintype "tri_state"))
    )
    (net (code "117") (name "unconnected-(IC5-SCK-Pad11)") (class "Default")
      (node (ref "IC5") (pin "11") (pinfunction "SCK_11") (pintype "input"))
    )
    (net (code "118") (name "unconnected-(IC5-SER-Pad14)") (class "Default")
      (node (ref "IC5") (pin "14") (pinfunction "SER_14") (pintype "input"))
    )
    (net (code "119") (name "unconnected-(IC6-QD-Pad3)") (class "Default")
      (node (ref "IC6") (pin "3") (pinfunction "QD_3") (pintype "tri_state"))
    )
    (net (code "120") (name "unconnected-(IC6-QG-Pad6)") (class "Default")
      (node (ref "IC6") (pin "6") (pinfunction "QG_6") (pintype "tri_state"))
    )
    (net (code "121") (name "unconnected-(IC6-SCK-Pad11)") (class "Default")
      (node (ref "IC6") (pin "11") (pinfunction "SCK_11") (pintype "input"))
    )
    (net (code "122") (name "unconnected-(IC6-SER-Pad14)") (class "Default")
      (node (ref "IC6") (pin "14") (pinfunction "SER_14") (pintype "input"))
    )
    (net (code "123") (name "unconnected-(IC7-QD-Pad3)") (class "Default")
      (node (ref "IC7") (pin "3") (pinfunction "QD_3") (pintype "tri_state"))
    )
    (net (code "124") (name "unconnected-(IC7-QG-Pad6)") (class "Default")
      (node (ref "IC7") (pin "6") (pinfunction "QG_6") (pintype "tri_state"))
    )
    (net (code "125") (name "unconnected-(IC7-SCK-Pad11)") (class "Default")
      (node (ref "IC7") (pin "11") (pinfunction "SCK_11") (pintype "input"))
    )
    (net (code "126") (name "unconnected-(IC7-SER-Pad14)") (class "Default")
      (node (ref "IC7") (pin "14") (pinfunction "SER_14") (pintype "input"))
    )
    (net (code "127") (name "unconnected-(IC8D-I0-Pad9)") (class "Default")
      (node (ref "IC8") (pin "9") (pinfunction "I0_9") (pintype "input"))
    )
    (net (code "128") (name "unconnected-(IC8D-I1-Pad8)") (class "Default")
      (node (ref "IC8") (pin "8") (pinfunction "I1_8") (pintype "input"))
    )
    (net (code "129") (name "unconnected-(IC8D-O-Pad7)") (class "Default")
      (node (ref "IC8") (pin "7") (pinfunction "O_7") (pintype "output"))
    )
    (net (code "130") (name "unconnected-(IC10A-A-Pad15)") (class "Default")
      (node (ref "IC10") (pin "15") (pinfunction "A_15") (pintype "input"))
    )
    (net (code "131") (name "unconnected-(IC10A-B-Pad1)") (class "Default")
      (node (ref "IC10") (pin "1") (pinfunction "B_1") (pintype "input"))
    )
    (net (code "132") (name "unconnected-(IC10A-BORROW-Pad13)") (class "Default")
      (node (ref "IC10") (pin "13") (pinfunction "BORROW_13") (pintype "output"))
    )
    (net (code "133") (name "unconnected-(IC10A-C-Pad10)") (class "Default")
      (node (ref "IC10") (pin "10") (pinfunction "C_10") (pintype "input"))
    )
    (net (code "134") (name "unconnected-(IC10A-CARRY-Pad12)") (class "Default")
      (node (ref "IC10") (pin "12") (pinfunction "CARRY_12") (pintype "output"))
    )
    (net (code "135") (name "unconnected-(IC10A-D-Pad9)") (class "Default")
      (node (ref "IC10") (pin "9") (pinfunction "D_9") (pintype "input"))
    )
    (net (code "136") (name "unconnected-(SPI0-Pad1)") (class "Default")
      (node (ref "SPI0") (pin "1") (pinfunction "1_1") (pintype "passive"))
    )
    (net (code "137") (name "unconnected-(SPI0-Pad2)") (class "Default")
      (node (ref "SPI0") (pin "2") (pinfunction "2_2") (pintype "passive"))
    )
    (net (code "138") (name "unconnected-(SPI0-Pad3)") (class "Default")
      (node (ref "SPI0") (pin "3") (pinfunction "3_3") (pintype "passive"))
    )
    (net (code "139") (name "unconnected-(SPI0-Pad4)") (class "Default")
      (node (ref "SPI0") (pin "4") (pinfunction "4_4") (pintype "passive"))
    )
    (net (code "140") (name "unconnected-(SPI0-Pad5)") (class "Default")
      (node (ref "SPI0") (pin "5") (pinfunction "5_5") (pintype "passive"))
    )
    (net (code "141") (name "unconnected-(SPI0-Pad6)") (class "Default")
      (node (ref "SPI0") (pin "6") (pinfunction "6_6") (pintype "passive"))
    )
    (net (code "142") (name "unconnected-(SPI1-Pad1)") (class "Default")
      (node (ref "SPI1") (pin "1") (pinfunction "1_1") (pintype "passive"))
    )
    (net (code "143") (name "unconnected-(SPI1-Pad2)") (class "Default")
      (node (ref "SPI1") (pin "2") (pinfunction "2_2") (pintype "passive"))
    )
    (net (code "144") (name "unconnected-(SPI1-Pad3)") (class "Default")
      (node (ref "SPI1") (pin "3") (pinfunction "3_3") (pintype "passive"))
    )
    (net (code "145") (name "unconnected-(SPI1-Pad4)") (class "Default")
      (node (ref "SPI1") (pin "4") (pinfunction "4_4") (pintype "passive"))
    )
    (net (code "146") (name "unconnected-(SPI1-Pad5)") (class "Default")
      (node (ref "SPI1") (pin "5") (pinfunction "5_5") (pintype "passive"))
    )
    (net (code "147") (name "unconnected-(SPI1-Pad6)") (class "Default")
      (node (ref "SPI1") (pin "6") (pinfunction "6_6") (pintype "passive"))
    )
    (net (code "148") (name "unconnected-(U1-NC-Pad63)") (class "Default")
      (node (ref "U1") (pin "63") (pinfunction "NC_63") (pintype "passive"))
    )
    (net (code "149") (name "unconnected-(U1-NC_2-Pad50)") (class "Default")
      (node (ref "U1") (pin "50") (pinfunction "NC_2_50") (pintype "passive"))
    )
    (net (code "150") (name "unconnected-(U1-NC_3-Pad51)") (class "Default")
      (node (ref "U1") (pin "51") (pinfunction "NC_3_51") (pintype "passive"))
    )
    (net (code "151") (name "unconnected-(U1-NC_4-Pad36)") (class "Default")
      (node (ref "U1") (pin "36") (pinfunction "NC_4_36") (pintype "passive"))
    )
    (net (code "152") (name "unconnected-(U1-NC_5-Pad62)") (class "Default")
      (node (ref "U1") (pin "62") (pinfunction "NC_5_62") (pintype "passive"))
    )
    (net (code "153") (name "unconnected-(U1-NC_6-Pad37)") (class "Default")
      (node (ref "U1") (pin "37") (pinfunction "NC_6_37") (pintype "passive"))
    )
    (net (code "154") (name "unconnected-(U1-REFCM-Pad19)") (class "Default")
      (node (ref "U1") (pin "19") (pinfunction "REFCM_19") (pintype "passive"))
    )
    (net (code "155") (name "unconnected-(U1-SOGIN0-Pad8)") (class "Default")
      (node (ref "U1") (pin "8") (pinfunction "SOGIN0_8") (pintype "passive"))
    )
    (net (code "156") (name "unconnected-(U1-SOGIN1-Pad12)") (class "Default")
      (node (ref "U1") (pin "12") (pinfunction "SOGIN1_12") (pintype "passive"))
    )
    (net (code "157") (name "unconnected-(U1-SOGOUT-Pad24)") (class "Default")
      (node (ref "U1") (pin "24") (pinfunction "SOGOUT_24") (pintype "passive"))
    )
    (net (code "158") (name "unconnected-(UART-Pad1)") (class "Default")
      (node (ref "UART") (pin "1") (pinfunction "1_1") (pintype "passive"))
    )
    (net (code "159") (name "unconnected-(UART-Pad2)") (class "Default")
      (node (ref "UART") (pin "2") (pinfunction "2_2") (pintype "passive"))
    )
    (net (code "160") (name "unconnected-(UART-Pad3)") (class "Default")
      (node (ref "UART") (pin "3") (pinfunction "3_3") (pintype "passive"))
    )
    (net (code "161") (name "unconnected-(UART-Pad4)") (class "Default")
      (node (ref "UART") (pin "4") (pinfunction "4_4") (pintype "passive"))
    )
  )
)
